# MAX3378_Regulado-v10.net
KiCad netlist of a schematic drawn in EAGLE
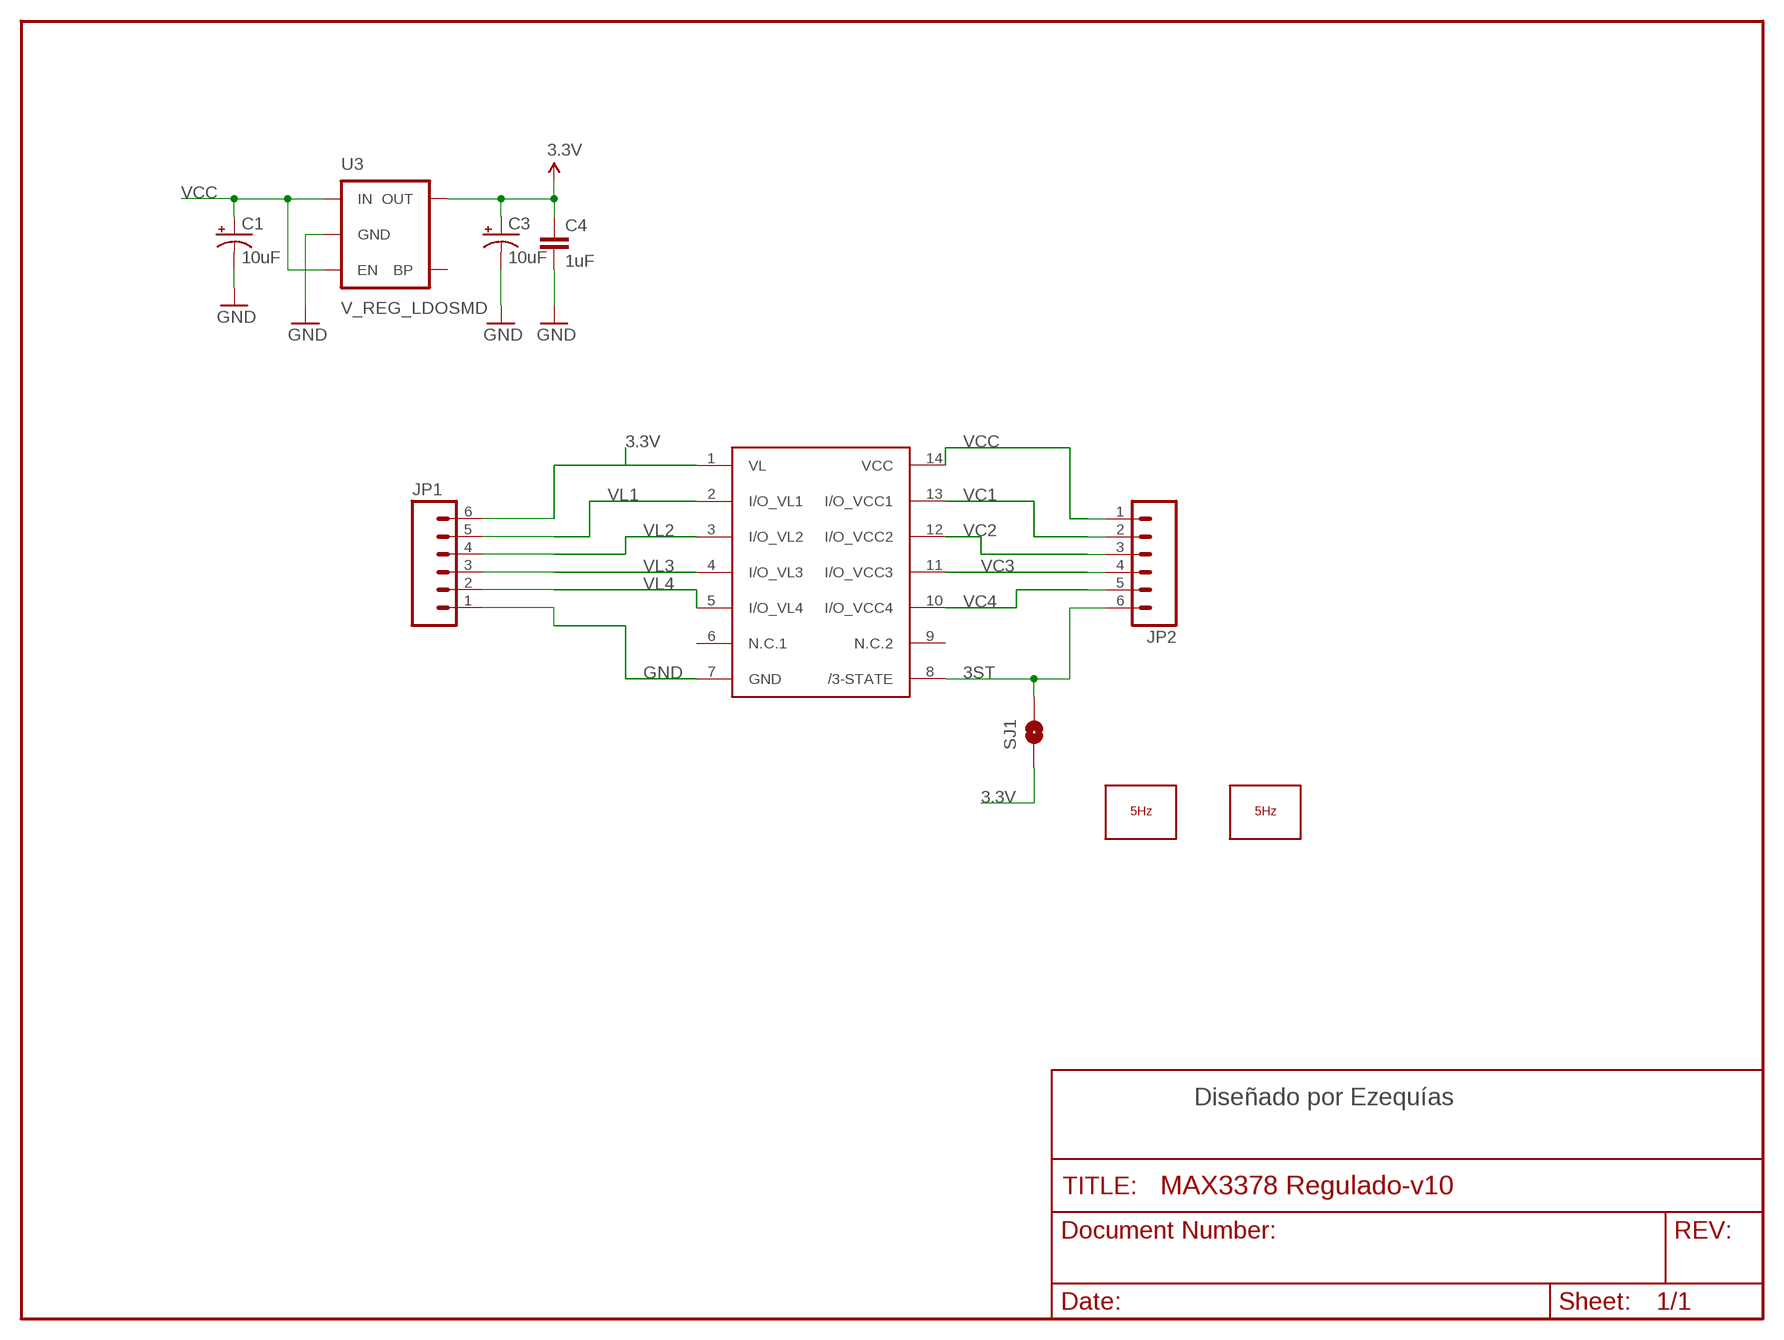
[diagram p0: schematic, sheet 1]

(export (version "E")
  (design (tool "Eeschema 10.0.6"))
  (components
    (comp (ref "C1")
      (value "10uF")
      (footprint "eagle-import:EIA3216")
      (libsource (lib "eagle-import") (part "CAP_POL1206"))
    )
    (comp (ref "C3")
      (value "10uF")
      (footprint "eagle-import:EIA3216")
      (libsource (lib "eagle-import") (part "CAP_POL1206"))
    )
    (comp (ref "C4")
      (value "1uF")
      (footprint "eagle-import:0603-CAP")
      (libsource (lib "eagle-import") (part "CAP0603-CAP"))
    )
    (comp (ref "JP1")
      (value "M06SIP")
      (footprint "eagle-import:1X06")
      (libsource (lib "eagle-import") (part "M06SIP"))
    )
    (comp (ref "JP2")
      (value "M06SIP")
      (footprint "eagle-import:1X06")
      (libsource (lib "eagle-import") (part "M06SIP"))
    )
    (comp (ref "LOGO1")
      (value "LOGO_5HZ_H_COOPER_15MM")
      (footprint "eagle-import:5HZ_LOGO_H_COOPER_15MM")
      (libsource (lib "eagle-import") (part "LOGO_5HZ_H_COOPER_15MM"))
    )
    (comp (ref "LOGO2")
      (value "LOGO_5HZ_WEB_10MM")
      (footprint "eagle-import:5HZ_WEB_10MM")
      (libsource (lib "eagle-import") (part "LOGO_5HZ_WEB_10MM"))
    )
    (comp (ref "SJ1")
      (value "SOLDERJUMPERNO")
      (footprint "eagle-import:SJ_2S-NO")
      (libsource (lib "eagle-import") (part "SOLDERJUMPERNO"))
    )
    (comp (ref "U$1")
      (value "MAX3378")
      (footprint "eagle-import:TSSOP14")
      (libsource (lib "eagle-import") (part "MAX3378"))
    )
    (comp (ref "U3")
      (value "V_REG_LDOSMD")
      (footprint "eagle-import:SOT23-5")
      (libsource (lib "eagle-import") (part "V_REG_LDOSMD"))
    )
  )
  (nets
    (net (code "1") (name "/3ST") (class "Default")
      (node (ref "JP2") (pin "6") (pinfunction "6_6") (pintype "passive"))
      (node (ref "SJ1") (pin "2") (pinfunction "2_2") (pintype "passive"))
      (node (ref "U$1") (pin "8") (pinfunction "/3-STATE_8") (pintype "bidirectional"))
    )
    (net (code "2") (name "/VC1") (class "Default")
      (node (ref "JP2") (pin "2") (pinfunction "2_2") (pintype "passive"))
      (node (ref "U$1") (pin "13") (pinfunction "I/O_VCC1_13") (pintype "bidirectional"))
    )
    (net (code "3") (name "/VC2") (class "Default")
      (node (ref "JP2") (pin "3") (pinfunction "3_3") (pintype "passive"))
      (node (ref "U$1") (pin "12") (pinfunction "I/O_VCC2_12") (pintype "bidirectional"))
    )
    (net (code "4") (name "/VC3") (class "Default")
      (node (ref "JP2") (pin "4") (pinfunction "4_4") (pintype "passive"))
      (node (ref "U$1") (pin "11") (pinfunction "I/O_VCC3_11") (pintype "bidirectional"))
    )
    (net (code "5") (name "/VC4") (class "Default")
      (node (ref "JP2") (pin "5") (pinfunction "5_5") (pintype "passive"))
      (node (ref "U$1") (pin "10") (pinfunction "I/O_VCC4_10") (pintype "bidirectional"))
    )
    (net (code "6") (name "/VCC") (class "Default")
      (node (ref "C1") (pin "A") (pinfunction "+_A") (pintype "passive"))
      (node (ref "JP2") (pin "1") (pinfunction "1_1") (pintype "passive"))
      (node (ref "U$1") (pin "14") (pinfunction "VCC_14") (pintype "bidirectional"))
      (node (ref "U3") (pin "1") (pinfunction "IN_1") (pintype "input"))
      (node (ref "U3") (pin "3") (pinfunction "EN_3") (pintype "input"))
    )
    (net (code "7") (name "/VL1") (class "Default")
      (node (ref "JP1") (pin "5") (pinfunction "5_5") (pintype "passive"))
      (node (ref "U$1") (pin "2") (pinfunction "I/O_VL1_2") (pintype "bidirectional"))
    )
    (net (code "8") (name "/VL2") (class "Default")
      (node (ref "JP1") (pin "4") (pinfunction "4_4") (pintype "passive"))
      (node (ref "U$1") (pin "3") (pinfunction "I/O_VL2_3") (pintype "bidirectional"))
    )
    (net (code "9") (name "/VL3") (class "Default")
      (node (ref "JP1") (pin "3") (pinfunction "3_3") (pintype "passive"))
      (node (ref "U$1") (pin "4") (pinfunction "I/O_VL3_4") (pintype "bidirectional"))
    )
    (net (code "10") (name "/VL4") (class "Default")
      (node (ref "JP1") (pin "2") (pinfunction "2_2") (pintype "passive"))
      (node (ref "U$1") (pin "5") (pinfunction "I/O_VL4_5") (pintype "bidirectional"))
    )
    (net (code "11") (name "3.3V") (class "Default")
      (node (ref "C3") (pin "A") (pinfunction "+_A") (pintype "passive"))
      (node (ref "C4") (pin "1") (pinfunction "1_1") (pintype "passive"))
      (node (ref "JP1") (pin "6") (pinfunction "6_6") (pintype "passive"))
      (node (ref "SJ1") (pin "1") (pinfunction "1_1") (pintype "passive"))
      (node (ref "U$1") (pin "1") (pinfunction "VL_1") (pintype "bidirectional"))
      (node (ref "U3") (pin "5") (pinfunction "OUT_5") (pintype "passive"))
    )
    (net (code "12") (name "GND") (class "Default")
      (node (ref "C1") (pin "C") (pinfunction "-_C") (pintype "passive"))
      (node (ref "C3") (pin "C") (pinfunction "-_C") (pintype "passive"))
      (node (ref "C4") (pin "2") (pinfunction "2_2") (pintype "passive"))
      (node (ref "JP1") (pin "1") (pinfunction "1_1") (pintype "passive"))
      (node (ref "U$1") (pin "7") (pinfunction "GND_7") (pintype "bidirectional"))
      (node (ref "U3") (pin "2") (pinfunction "GND_2") (pintype "input"))
    )
    (net (code "13") (name "unconnected-(U$1-N.C.1-Pad6)") (class "Default")
      (node (ref "U$1") (pin "6") (pinfunction "N.C.1_6") (pintype "bidirectional"))
    )
    (net (code "14") (name "unconnected-(U$1-N.C.2-Pad9)") (class "Default")
      (node (ref "U$1") (pin "9") (pinfunction "N.C.2_9") (pintype "bidirectional"))
    )
    (net (code "15") (name "unconnected-(U3-BP-Pad4)") (class "Default")
      (node (ref "U3") (pin "4") (pinfunction "BP_4") (pintype "input"))
    )
  )
)
